# HF1R0.net
KiCad netlist of a schematic drawn in EAGLE
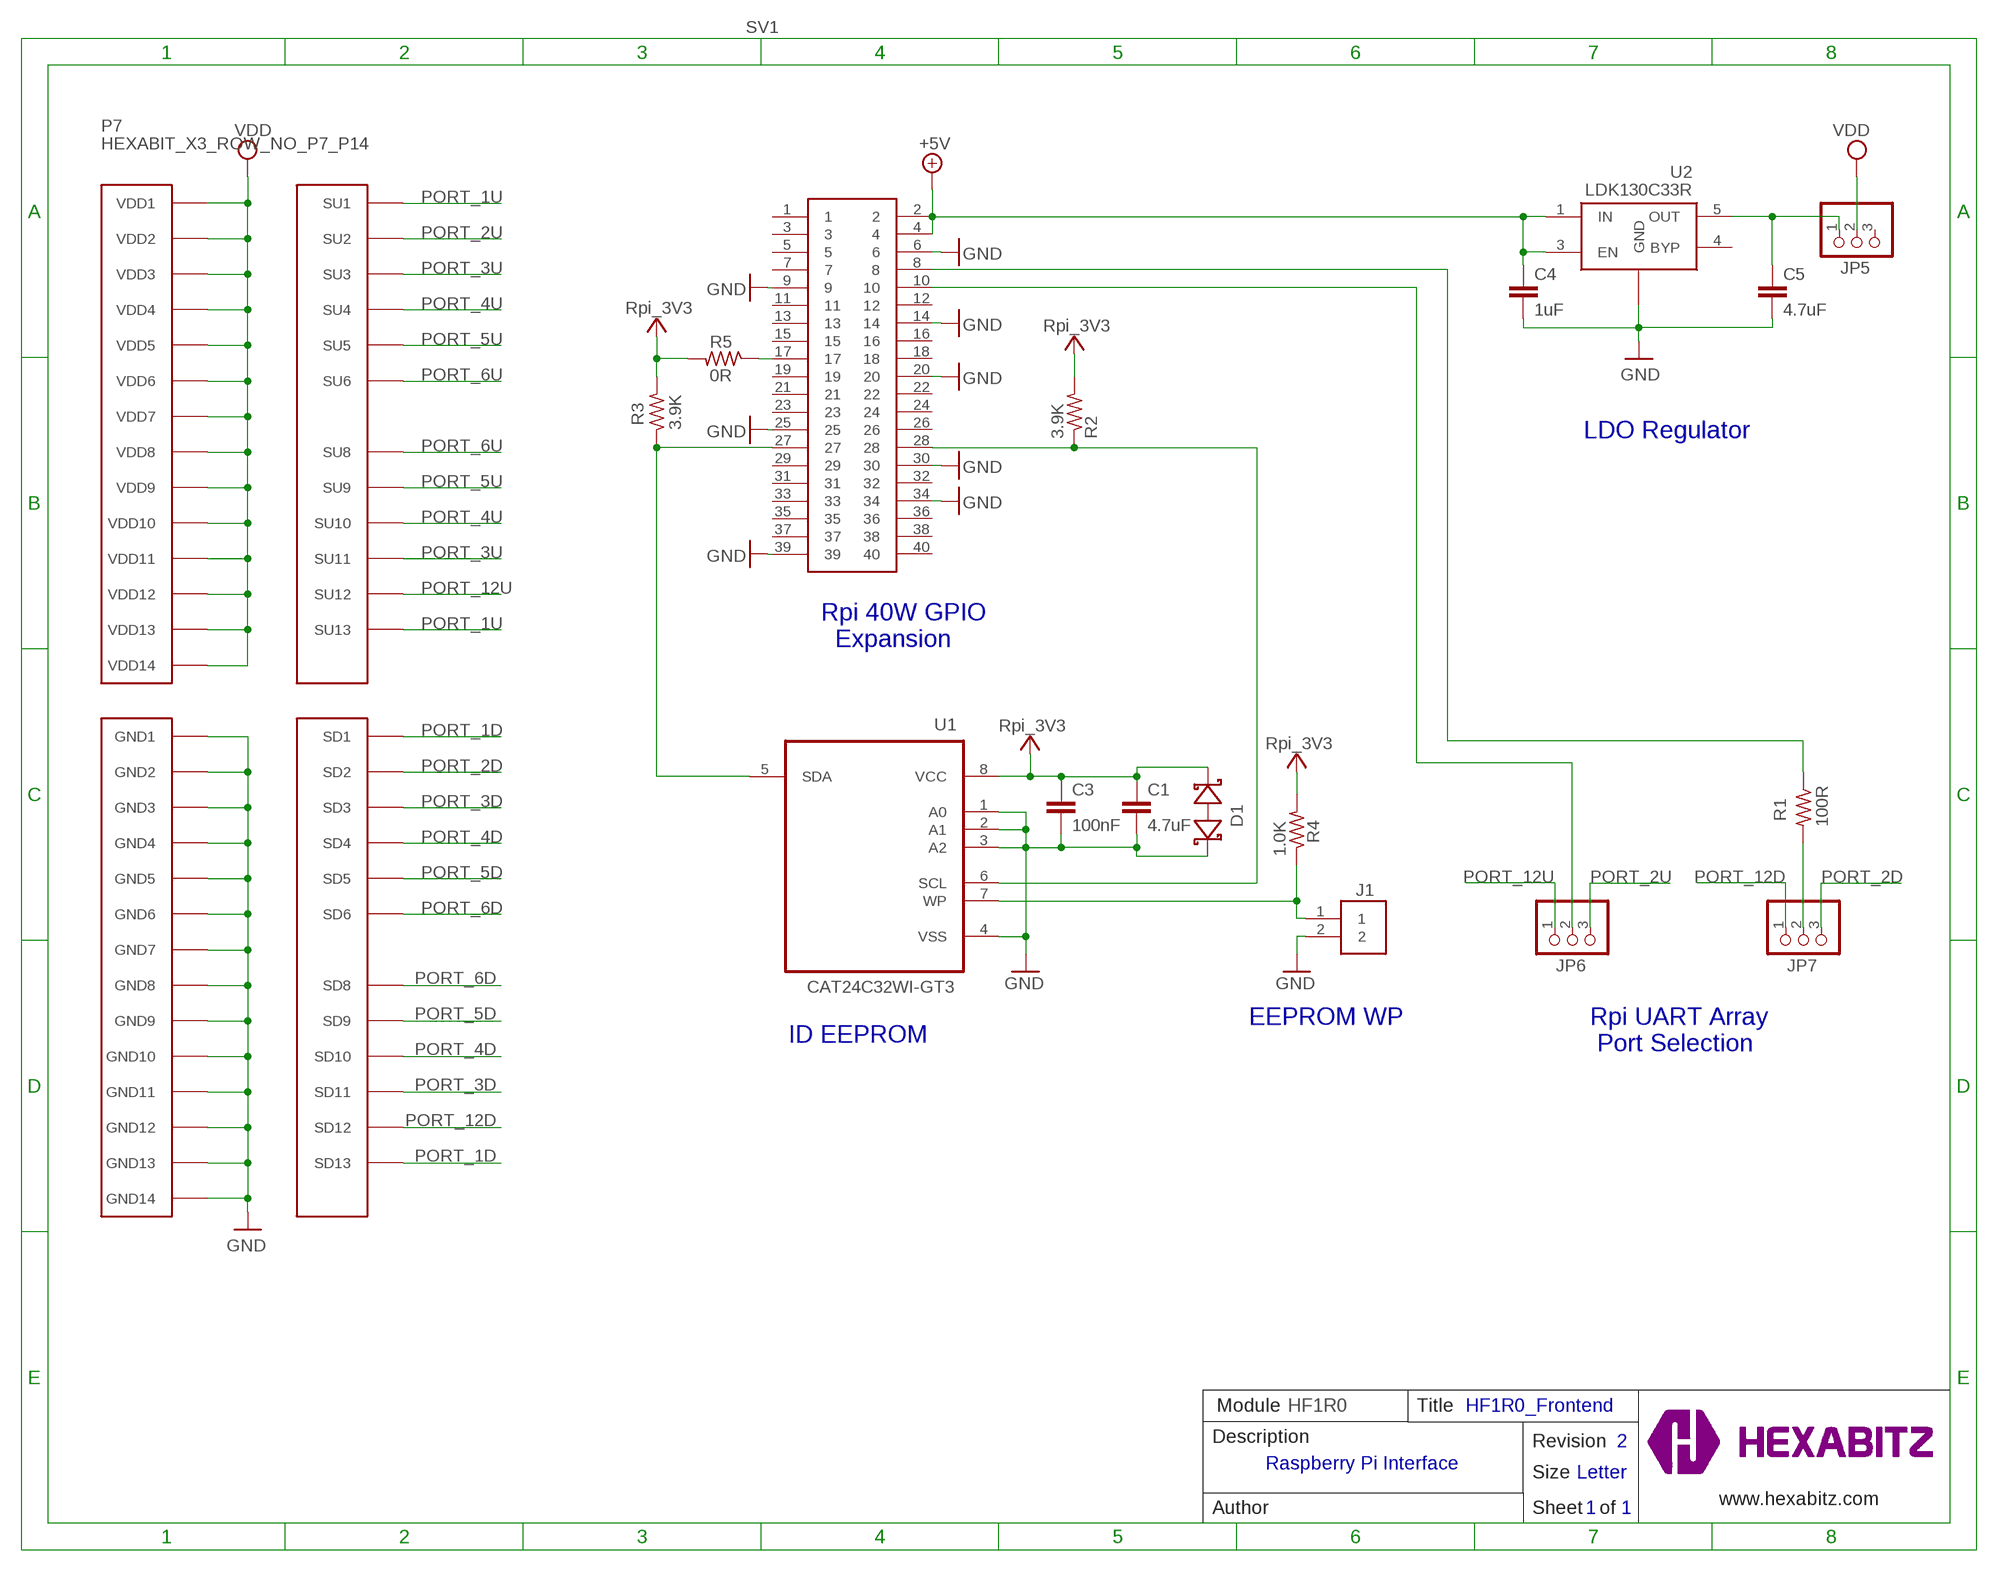
[diagram p0: schematic, sheet 1]

(export (version "E")
  (design (tool "Eeschema 10.0.6"))
  (components
    (comp (ref "C1")
      (value "4.7uF")
      (footprint "eagle-import:C-0805")
      (libsource (lib "eagle-import") (part "C-0805"))
    )
    (comp (ref "C3")
      (value "100nF")
      (footprint "eagle-import:C-0603")
      (fields
        (field (name "CAPACITANCE") "100nF")
        (field (name "MFN") "KEMET")
        (field (name "MPN") "C0603C104K8RACTU")
        (field (name "OCTOPART_URL") "https://octopart.com/c0603c104k8ractu-kemet-145075?r=sp&s=9bS9ASSwSEqMCE9KBEQZ0g")
        (field (name "TOLERANCE") "10V")
        (field (name "VOLTAGE_RATING") "10%")
      )
      (libsource (lib "eagle-import") (part "C-0603"))
    )
    (comp (ref "C4")
      (value "1uF")
      (footprint "eagle-import:C-0805")
      (libsource (lib "eagle-import") (part "C-0805"))
    )
    (comp (ref "C5")
      (value "4.7uF")
      (footprint "eagle-import:C-0805")
      (libsource (lib "eagle-import") (part "C-0805"))
    )
    (comp (ref "D1")
      (value "BOURNS_CDSOD323-T03SCBOURNS_CDSOD323-T03SC_0_0")
      (footprint "eagle-import:BOURNS_CDSOD323-T03SC_0")
      (fields (field (name "MPN") "CDSOD323-T03SC"))
      (libsource (lib "eagle-import") (part "BOURNS_CDSOD323-T03SCBOURNS_CDSOD323-T03SC_0_0"))
    )
    (comp (ref "J1")
      (value "3-644456-2")
      (footprint "eagle-import:TE_3-644456-2")
      (fields (field (name "MF") "TE Connectivity") (field (name "MPN") "87224-1"))
      (libsource (lib "eagle-import") (part "3-644456-2"))
    )
    (comp (ref "JP5")
      (value "PINHD-1X3")
      (footprint "eagle-import:1X03")
      (libsource (lib "eagle-import") (part "PINHD-1X3"))
    )
    (comp (ref "JP6")
      (value "PINHD-1X3")
      (footprint "eagle-import:1X03")
      (libsource (lib "eagle-import") (part "PINHD-1X3"))
    )
    (comp (ref "JP7")
      (value "PINHD-1X3")
      (footprint "eagle-import:1X03")
      (libsource (lib "eagle-import") (part "PINHD-1X3"))
    )
    (comp (ref "P7")
      (value "HEXABIT_X3_ROW_NO_P7_P14")
      (footprint "eagle-import:HEXABIT_X3_ROW_NO_P7_P14")
      (libsource (lib "eagle-import") (part "HEXABIT_X3_ROW_NO_P7_P14"))
    )
    (comp (ref "R1")
      (value "100R")
      (footprint "eagle-import:R-0603")
      (fields
        (field (name "MFN") "Panasonic ")
        (field (name "MPN") "ERJ-PA3F1000V")
        (field (name "OCTOPART_URL") "https://octopart.com/erj-pa3f1000v-panasonic-51302178?r=sp&s=FtfQlVmZQ6G_o34px3VECw")
        (field (name "RESISTANCE") "100.0 Ohm")
        (field (name "TOLERANCE") "1%")
      )
      (libsource (lib "eagle-import") (part "R-0603"))
    )
    (comp (ref "R2")
      (value "3.9K")
      (footprint "eagle-import:R-0603")
      (fields
        (field (name "MFN") "Vishay")
        (field (name "MPN") "CRCW06033K90FKEA")
        (field (name "OCTOPART_URL") "https://octopart.com/crcw06033k90fkea-vishay-40019003?r=sp&s=g-tYgB-WSDSQxdPWmNeinA")
        (field (name "RESISTANCE") "3.9 kOhm")
        (field (name "TOLERANCE") "1%")
      )
      (libsource (lib "eagle-import") (part "R-0603"))
    )
    (comp (ref "R3")
      (value "3.9K")
      (footprint "eagle-import:R-0603")
      (fields
        (field (name "MFN") "Vishay")
        (field (name "MPN") "CRCW06033K90FKEA")
        (field (name "OCTOPART_URL") "https://octopart.com/crcw06033k90fkea-vishay-40019003?r=sp&s=g-tYgB-WSDSQxdPWmNeinA")
        (field (name "RESISTANCE") "3.9 kOhm")
        (field (name "TOLERANCE") "1%")
      )
      (libsource (lib "eagle-import") (part "R-0603"))
    )
    (comp (ref "R4")
      (value "1.0K")
      (footprint "eagle-import:R-0603")
      (fields
        (field (name "MFN") "Panasonic")
        (field (name "MPN") "ERJ-3EKF1001V")
        (field (name "OCTOPART_URL") "https://octopart.com/erj-3ekf1001v-panasonic-55403646?r=sp&s=_UtQAJDmTsiNho0Uqf11iA")
        (field (name "RESISTANCE") "1.0 kOhm")
        (field (name "TOLERANCE") "1%")
      )
      (libsource (lib "eagle-import") (part "R-0603"))
    )
    (comp (ref "R5")
      (value "0R")
      (footprint "eagle-import:R-0603")
      (fields
        (field (name "MFN") "Vishay")
        (field (name "MPN") "CRCW06033K90FKEA")
        (field (name "OCTOPART_URL") "https://octopart.com/crcw06033k90fkea-vishay-40019003?r=sp&s=g-tYgB-WSDSQxdPWmNeinA")
        (field (name "RESISTANCE") "3.9 kOhm")
        (field (name "TOLERANCE") "1%")
      )
      (libsource (lib "eagle-import") (part "R-0603"))
    )
    (comp (ref "SV1")
      (value "PPTC202LFBN-RC")
      (footprint "eagle-import:RHDR40W64P254X254_2X20_5105X50")
      (fields (field (name "ARROW_PART_NUMBER") "2223") (field (name "MOUSER_PART_NUMBER") "485-2223"))
      (libsource (lib "eagle-import") (part "2223"))
    )
    (comp (ref "TRIMBLE-LOGO2")
      (value "HEXABITZ-LOGO")
      (footprint "eagle-import:HEXABITZ-LOGO")
      (libsource (lib "eagle-import") (part "HEXABITZ-LOGO"))
    )
    (comp (ref "U1")
      (value "CAT24C32WI-GT3")
      (footprint "eagle-import:SOIC127P600X175-8N")
      (libsource (lib "eagle-import") (part "CAT24C32WI-GT3"))
    )
    (comp (ref "U2")
      (value "LDK130C33R")
      (footprint "eagle-import:SOT65P210X110-5N")
      (fields (field (name "MOUSER_PART_NUMBER") "511-LDK130C33R"))
      (libsource (lib "eagle-import") (part "LDK130C33R"))
    )
  )
  (nets
    (net (code "1") (name "+5V") (class "Default")
      (node (ref "C4") (pin "1") (pinfunction "1_1") (pintype "passive"))
      (node (ref "SV1") (pin "2") (pinfunction "2_2") (pintype "bidirectional"))
      (node (ref "SV1") (pin "4") (pinfunction "4_4") (pintype "bidirectional"))
      (node (ref "U2") (pin "1") (pinfunction "IN_1") (pintype "bidirectional"))
      (node (ref "U2") (pin "3") (pinfunction "EN_3") (pintype "bidirectional"))
    )
    (net (code "2") (name "/PORT_1D") (class "Default")
      (node (ref "P7") (pin "PAD_PD1") (pinfunction "SD1_PAD_PD1") (pintype "bidirectional"))
      (node (ref "P7") (pin "PAD_PD13") (pinfunction "SD13_PAD_PD13") (pintype "bidirectional"))
    )
    (net (code "3") (name "/PORT_1U") (class "Default")
      (node (ref "P7") (pin "PAD_PU1") (pinfunction "SU1_PAD_PU1") (pintype "bidirectional"))
      (node (ref "P7") (pin "PAD_PU13") (pinfunction "SU13_PAD_PU13") (pintype "bidirectional"))
    )
    (net (code "4") (name "/PORT_2D") (class "Default")
      (node (ref "JP7") (pin "3") (pinfunction "3_3") (pintype "passive"))
      (node (ref "P7") (pin "PAD_PD2") (pinfunction "SD2_PAD_PD2") (pintype "bidirectional"))
    )
    (net (code "5") (name "/PORT_2U") (class "Default")
      (node (ref "JP6") (pin "3") (pinfunction "3_3") (pintype "passive"))
      (node (ref "P7") (pin "PAD_PU2") (pinfunction "SU2_PAD_PU2") (pintype "bidirectional"))
    )
    (net (code "6") (name "/PORT_3D") (class "Default")
      (node (ref "P7") (pin "PAD_PD11") (pinfunction "SD11_PAD_PD11") (pintype "bidirectional"))
      (node (ref "P7") (pin "PAD_PD3") (pinfunction "SD3_PAD_PD3") (pintype "bidirectional"))
    )
    (net (code "7") (name "/PORT_3U") (class "Default")
      (node (ref "P7") (pin "PAD_PU11") (pinfunction "SU11_PAD_PU11") (pintype "bidirectional"))
      (node (ref "P7") (pin "PAD_PU3") (pinfunction "SU3_PAD_PU3") (pintype "bidirectional"))
    )
    (net (code "8") (name "/PORT_4D") (class "Default")
      (node (ref "P7") (pin "PAD_PD10") (pinfunction "SD10_PAD_PD10") (pintype "bidirectional"))
      (node (ref "P7") (pin "PAD_PD4") (pinfunction "SD4_PAD_PD4") (pintype "bidirectional"))
    )
    (net (code "9") (name "/PORT_4U") (class "Default")
      (node (ref "P7") (pin "PAD_PU10") (pinfunction "SU10_PAD_PU10") (pintype "bidirectional"))
      (node (ref "P7") (pin "PAD_PU4") (pinfunction "SU4_PAD_PU4") (pintype "bidirectional"))
    )
    (net (code "10") (name "/PORT_5D") (class "Default")
      (node (ref "P7") (pin "PAD_PD5") (pinfunction "SD5_PAD_PD5") (pintype "bidirectional"))
      (node (ref "P7") (pin "PAD_PD9") (pinfunction "SD9_PAD_PD9") (pintype "bidirectional"))
    )
    (net (code "11") (name "/PORT_5U") (class "Default")
      (node (ref "P7") (pin "PAD_PU5") (pinfunction "SU5_PAD_PU5") (pintype "bidirectional"))
      (node (ref "P7") (pin "PAD_PU9") (pinfunction "SU9_PAD_PU9") (pintype "bidirectional"))
    )
    (net (code "12") (name "/PORT_6D") (class "Default")
      (node (ref "P7") (pin "PAD_PD6") (pinfunction "SD6_PAD_PD6") (pintype "bidirectional"))
      (node (ref "P7") (pin "PAD_PD8") (pinfunction "SD8_PAD_PD8") (pintype "bidirectional"))
    )
    (net (code "13") (name "/PORT_6U") (class "Default")
      (node (ref "P7") (pin "PAD_PU6") (pinfunction "SU6_PAD_PU6") (pintype "bidirectional"))
      (node (ref "P7") (pin "PAD_PU8") (pinfunction "SU8_PAD_PU8") (pintype "bidirectional"))
    )
    (net (code "14") (name "/PORT_12D") (class "Default")
      (node (ref "JP7") (pin "1") (pinfunction "1_1") (pintype "passive"))
      (node (ref "P7") (pin "PAD_PD12") (pinfunction "SD12_PAD_PD12") (pintype "bidirectional"))
    )
    (net (code "15") (name "/PORT_12U") (class "Default")
      (node (ref "JP6") (pin "1") (pinfunction "1_1") (pintype "passive"))
      (node (ref "P7") (pin "PAD_PU12") (pinfunction "SU12_PAD_PU12") (pintype "bidirectional"))
    )
    (net (code "16") (name "GND") (class "Default")
      (node (ref "C1") (pin "2") (pinfunction "2_2") (pintype "passive"))
      (node (ref "C3") (pin "2") (pinfunction "2_2") (pintype "passive"))
      (node (ref "C4") (pin "2") (pinfunction "2_2") (pintype "passive"))
      (node (ref "C5") (pin "2") (pinfunction "2_2") (pintype "passive"))
      (node (ref "D1") (pin "1") (pinfunction "A_1") (pintype "passive"))
      (node (ref "J1") (pin "2") (pinfunction "2_2") (pintype "passive"))
      (node (ref "P7") (pin "PAD_PD15") (pinfunction "GND1_PAD_PD15") (pintype "power_in"))
      (node (ref "P7") (pin "PAD_PD16") (pinfunction "GND2_PAD_PD16") (pintype "power_in"))
      (node (ref "P7") (pin "PAD_PD17") (pinfunction "GND3_PAD_PD17") (pintype "power_in"))
      (node (ref "P7") (pin "PAD_PD18") (pinfunction "GND4_PAD_PD18") (pintype "power_in"))
      (node (ref "P7") (pin "PAD_PD19") (pinfunction "GND5_PAD_PD19") (pintype "power_in"))
      (node (ref "P7") (pin "PAD_PD20") (pinfunction "GND6_PAD_PD20") (pintype "power_in"))
      (node (ref "P7") (pin "PAD_PD21") (pinfunction "GND7_PAD_PD21") (pintype "power_in"))
      (node (ref "P7") (pin "PAD_PD22") (pinfunction "GND8_PAD_PD22") (pintype "power_in"))
      (node (ref "P7") (pin "PAD_PD23") (pinfunction "GND9_PAD_PD23") (pintype "power_in"))
      (node (ref "P7") (pin "PAD_PD24") (pinfunction "GND10_PAD_PD24") (pintype "power_in"))
      (node (ref "P7") (pin "PAD_PD25") (pinfunction "GND11_PAD_PD25") (pintype "power_in"))
      (node (ref "P7") (pin "PAD_PD26") (pinfunction "GND12_PAD_PD26") (pintype "power_in"))
      (node (ref "P7") (pin "PAD_PD27") (pinfunction "GND13_PAD_PD27") (pintype "power_in"))
      (node (ref "P7") (pin "PAD_PD28") (pinfunction "GND14_PAD_PD28") (pintype "power_in"))
      (node (ref "SV1") (pin "14") (pinfunction "14_14") (pintype "bidirectional"))
      (node (ref "SV1") (pin "20") (pinfunction "20_20") (pintype "bidirectional"))
      (node (ref "SV1") (pin "25") (pinfunction "25_25") (pintype "bidirectional"))
      (node (ref "SV1") (pin "30") (pinfunction "30_30") (pintype "bidirectional"))
      (node (ref "SV1") (pin "34") (pinfunction "34_34") (pintype "bidirectional"))
      (node (ref "SV1") (pin "39") (pinfunction "39_39") (pintype "bidirectional"))
      (node (ref "SV1") (pin "6") (pinfunction "6_6") (pintype "bidirectional"))
      (node (ref "SV1") (pin "9") (pinfunction "9_9") (pintype "bidirectional"))
      (node (ref "U1") (pin "1") (pinfunction "A0_1") (pintype "input"))
      (node (ref "U1") (pin "2") (pinfunction "A1_2") (pintype "input"))
      (node (ref "U1") (pin "3") (pinfunction "A2_3") (pintype "input"))
      (node (ref "U1") (pin "4") (pinfunction "VSS_4") (pintype "passive"))
      (node (ref "U2") (pin "2") (pinfunction "GND_2") (pintype "bidirectional"))
    )
    (net (code "17") (name "Net-(JP6-Pad2)") (class "Default")
      (node (ref "JP6") (pin "2") (pinfunction "2_2") (pintype "passive"))
      (node (ref "SV1") (pin "10") (pinfunction "10_10") (pintype "bidirectional"))
    )
    (net (code "18") (name "Net-(JP7-Pad2)") (class "Default")
      (node (ref "JP7") (pin "2") (pinfunction "2_2") (pintype "passive"))
      (node (ref "R1") (pin "2") (pinfunction "2_2") (pintype "passive"))
    )
    (net (code "19") (name "Net-(R1-Pad1)") (class "Default")
      (node (ref "R1") (pin "1") (pinfunction "1_1") (pintype "passive"))
      (node (ref "SV1") (pin "8") (pinfunction "8_8") (pintype "bidirectional"))
    )
    (net (code "20") (name "Net-(R5-Pad1)") (class "Default")
      (node (ref "R5") (pin "1") (pinfunction "1_1") (pintype "passive"))
      (node (ref "SV1") (pin "17") (pinfunction "17_17") (pintype "bidirectional"))
    )
    (net (code "21") (name "Net-(U1-SCL)") (class "Default")
      (node (ref "R2") (pin "1") (pinfunction "1_1") (pintype "passive"))
      (node (ref "SV1") (pin "28") (pinfunction "28_28") (pintype "bidirectional"))
      (node (ref "U1") (pin "6") (pinfunction "SCL_6") (pintype "input"))
    )
    (net (code "22") (name "Net-(U1-SDA)") (class "Default")
      (node (ref "R3") (pin "1") (pinfunction "1_1") (pintype "passive"))
      (node (ref "SV1") (pin "27") (pinfunction "27_27") (pintype "bidirectional"))
      (node (ref "U1") (pin "5") (pinfunction "SDA_5") (pintype "bidirectional"))
    )
    (net (code "23") (name "Net-(U1-WP)") (class "Default")
      (node (ref "J1") (pin "1") (pinfunction "1_1") (pintype "passive"))
      (node (ref "R4") (pin "1") (pinfunction "1_1") (pintype "passive"))
      (node (ref "U1") (pin "7") (pinfunction "WP_7") (pintype "input"))
    )
    (net (code "24") (name "Net-(U2-OUT)") (class "Default")
      (node (ref "C5") (pin "1") (pinfunction "1_1") (pintype "passive"))
      (node (ref "JP5") (pin "1") (pinfunction "1_1") (pintype "passive"))
      (node (ref "U2") (pin "5") (pinfunction "OUT_5") (pintype "bidirectional"))
    )
    (net (code "25") (name "Rpi_3V3") (class "Default")
      (node (ref "C1") (pin "1") (pinfunction "1_1") (pintype "passive"))
      (node (ref "C3") (pin "1") (pinfunction "1_1") (pintype "passive"))
      (node (ref "D1") (pin "2") (pinfunction "C_2") (pintype "passive"))
      (node (ref "R2") (pin "2") (pinfunction "2_2") (pintype "passive"))
      (node (ref "R3") (pin "2") (pinfunction "2_2") (pintype "passive"))
      (node (ref "R4") (pin "2") (pinfunction "2_2") (pintype "passive"))
      (node (ref "R5") (pin "2") (pinfunction "2_2") (pintype "passive"))
      (node (ref "U1") (pin "8") (pinfunction "VCC_8") (pintype "power_in"))
    )
    (net (code "26") (name "VDD") (class "Default")
      (node (ref "JP5") (pin "2") (pinfunction "2_2") (pintype "passive"))
      (node (ref "P7") (pin "PAD_PU15") (pinfunction "VDD1_PAD_PU15") (pintype "power_in"))
      (node (ref "P7") (pin "PAD_PU16") (pinfunction "VDD2_PAD_PU16") (pintype "power_in"))
      (node (ref "P7") (pin "PAD_PU17") (pinfunction "VDD3_PAD_PU17") (pintype "power_in"))
      (node (ref "P7") (pin "PAD_PU18") (pinfunction "VDD4_PAD_PU18") (pintype "power_in"))
      (node (ref "P7") (pin "PAD_PU19") (pinfunction "VDD5_PAD_PU19") (pintype "power_in"))
      (node (ref "P7") (pin "PAD_PU20") (pinfunction "VDD6_PAD_PU20") (pintype "power_in"))
      (node (ref "P7") (pin "PAD_PU21") (pinfunction "VDD7_PAD_PU21") (pintype "power_in"))
      (node (ref "P7") (pin "PAD_PU22") (pinfunction "VDD8_PAD_PU22") (pintype "power_in"))
      (node (ref "P7") (pin "PAD_PU23") (pinfunction "VDD9_PAD_PU23") (pintype "power_in"))
      (node (ref "P7") (pin "PAD_PU24") (pinfunction "VDD10_PAD_PU24") (pintype "power_in"))
      (node (ref "P7") (pin "PAD_PU25") (pinfunction "VDD11_PAD_PU25") (pintype "power_in"))
      (node (ref "P7") (pin "PAD_PU26") (pinfunction "VDD12_PAD_PU26") (pintype "power_in"))
      (node (ref "P7") (pin "PAD_PU27") (pinfunction "VDD13_PAD_PU27") (pintype "power_in"))
      (node (ref "P7") (pin "PAD_PU28") (pinfunction "VDD14_PAD_PU28") (pintype "power_in"))
    )
    (net (code "27") (name "unconnected-(JP5-Pad3)") (class "Default")
      (node (ref "JP5") (pin "3") (pinfunction "3_3") (pintype "passive"))
    )
    (net (code "28") (name "unconnected-(SV1-Pad1)") (class "Default")
      (node (ref "SV1") (pin "1") (pinfunction "1_1") (pintype "bidirectional"))
    )
    (net (code "29") (name "unconnected-(SV1-Pad3)") (class "Default")
      (node (ref "SV1") (pin "3") (pinfunction "3_3") (pintype "bidirectional"))
    )
    (net (code "30") (name "unconnected-(SV1-Pad5)") (class "Default")
      (node (ref "SV1") (pin "5") (pinfunction "5_5") (pintype "bidirectional"))
    )
    (net (code "31") (name "unconnected-(SV1-Pad7)") (class "Default")
      (node (ref "SV1") (pin "7") (pinfunction "7_7") (pintype "bidirectional"))
    )
    (net (code "32") (name "unconnected-(SV1-Pad11)") (class "Default")
      (node (ref "SV1") (pin "11") (pinfunction "11_11") (pintype "bidirectional"))
    )
    (net (code "33") (name "unconnected-(SV1-Pad12)") (class "Default")
      (node (ref "SV1") (pin "12") (pinfunction "12_12") (pintype "bidirectional"))
    )
    (net (code "34") (name "unconnected-(SV1-Pad13)") (class "Default")
      (node (ref "SV1") (pin "13") (pinfunction "13_13") (pintype "bidirectional"))
    )
    (net (code "35") (name "unconnected-(SV1-Pad15)") (class "Default")
      (node (ref "SV1") (pin "15") (pinfunction "15_15") (pintype "bidirectional"))
    )
    (net (code "36") (name "unconnected-(SV1-Pad16)") (class "Default")
      (node (ref "SV1") (pin "16") (pinfunction "16_16") (pintype "bidirectional"))
    )
    (net (code "37") (name "unconnected-(SV1-Pad18)") (class "Default")
      (node (ref "SV1") (pin "18") (pinfunction "18_18") (pintype "bidirectional"))
    )
    (net (code "38") (name "unconnected-(SV1-Pad19)") (class "Default")
      (node (ref "SV1") (pin "19") (pinfunction "19_19") (pintype "bidirectional"))
    )
    (net (code "39") (name "unconnected-(SV1-Pad21)") (class "Default")
      (node (ref "SV1") (pin "21") (pinfunction "21_21") (pintype "bidirectional"))
    )
    (net (code "40") (name "unconnected-(SV1-Pad22)") (class "Default")
      (node (ref "SV1") (pin "22") (pinfunction "22_22") (pintype "bidirectional"))
    )
    (net (code "41") (name "unconnected-(SV1-Pad23)") (class "Default")
      (node (ref "SV1") (pin "23") (pinfunction "23_23") (pintype "bidirectional"))
    )
    (net (code "42") (name "unconnected-(SV1-Pad24)") (class "Default")
      (node (ref "SV1") (pin "24") (pinfunction "24_24") (pintype "bidirectional"))
    )
    (net (code "43") (name "unconnected-(SV1-Pad26)") (class "Default")
      (node (ref "SV1") (pin "26") (pinfunction "26_26") (pintype "bidirectional"))
    )
    (net (code "44") (name "unconnected-(SV1-Pad29)") (class "Default")
      (node (ref "SV1") (pin "29") (pinfunction "29_29") (pintype "bidirectional"))
    )
    (net (code "45") (name "unconnected-(SV1-Pad31)") (class "Default")
      (node (ref "SV1") (pin "31") (pinfunction "31_31") (pintype "bidirectional"))
    )
    (net (code "46") (name "unconnected-(SV1-Pad32)") (class "Default")
      (node (ref "SV1") (pin "32") (pinfunction "32_32") (pintype "bidirectional"))
    )
    (net (code "47") (name "unconnected-(SV1-Pad33)") (class "Default")
      (node (ref "SV1") (pin "33") (pinfunction "33_33") (pintype "bidirectional"))
    )
    (net (code "48") (name "unconnected-(SV1-Pad35)") (class "Default")
      (node (ref "SV1") (pin "35") (pinfunction "35_35") (pintype "bidirectional"))
    )
    (net (code "49") (name "unconnected-(SV1-Pad36)") (class "Default")
      (node (ref "SV1") (pin "36") (pinfunction "36_36") (pintype "bidirectional"))
    )
    (net (code "50") (name "unconnected-(SV1-Pad37)") (class "Default")
      (node (ref "SV1") (pin "37") (pinfunction "37_37") (pintype "bidirectional"))
    )
    (net (code "51") (name "unconnected-(SV1-Pad38)") (class "Default")
      (node (ref "SV1") (pin "38") (pinfunction "38_38") (pintype "bidirectional"))
    )
    (net (code "52") (name "unconnected-(SV1-Pad40)") (class "Default")
      (node (ref "SV1") (pin "40") (pinfunction "40_40") (pintype "bidirectional"))
    )
    (net (code "53") (name "unconnected-(U2-BYP-Pad4)") (class "Default")
      (node (ref "U2") (pin "4") (pinfunction "BYP_4") (pintype "bidirectional"))
    )
  )
)
